# nagnet.net
KiCad netlist of a schematic drawn in Altium Designer
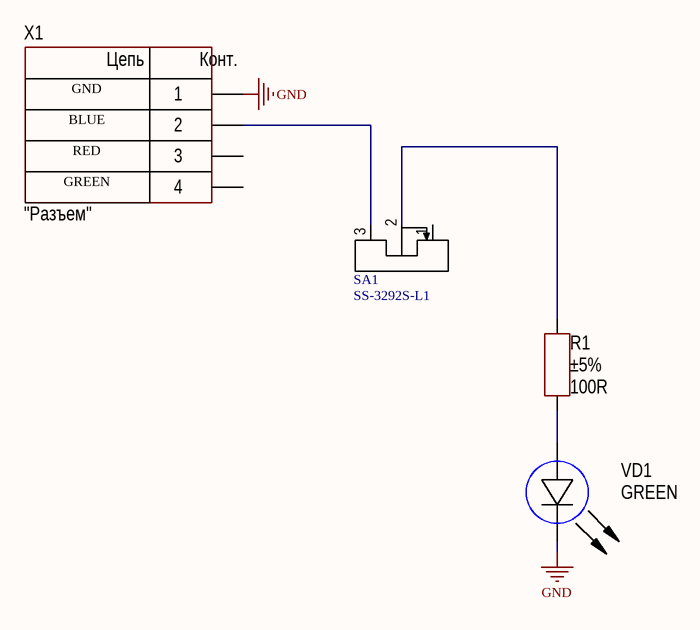
[diagram p0: nagnet.SchDoc]

(export (version "E")
  (design (tool "Eeschema 10.0.6"))
  (components
    (comp (ref "R1")
      (value "100R")
      (footprint "RES: 0603")
      (fields
        (field (name "MANUFACTURER") "Yageo")
        (field (name "PARTNUMBER") "RC0603JR-07100RL")
        (field (name "VALUEMANUFACTURERPARTNUMBER") "Resistor film, 100R, ±5%, 0603, 0.1W, -55...+125°C")
        (field (name "TOLERANCE") "±5%")
      )
      (libsource (lib "Resistor") (part "Resistor_0603"))
    )
    (comp (ref "SA1")
      (value "SS-3292S-L1")
      (footprint "SS-3292S-L1")
      (libsource (lib "switch") (part "SS-3292S-L1"))
    )
    (comp (ref "VD1")
      (value "~")
      (footprint "LED: 1206R")
      (fields
        (field (name "VALUEMANUFACTURERPARTNUMBER") "LED, *, *, *, -55...+150°C")
        (field (name "COLOR") "GREEN")
      )
      (libsource (lib "Diode") (part "LED_single"))
    )
    (comp (ref "X1")
      (value "~")
      (footprint "CON: PBS-4 R")
      (fields
        (field (name "MANUFACTURER") "Connfly")
        (field (name "VALUEMANUFACTURERPARTNUMBER") "Connector, 4pin, 2.54mm, 500VAC, 3A")
        (field (name "PARTNUMBER") "PBS-4")
        (field (name "COMMENTTEXT") "\"Разъем\"")
      )
      (libsource (lib "Connector") (part "PBS-4"))
    )
  )
  (nets
    (net (code "1") (name "GND") (class "Default")
      (node (ref "VD1") (pin "2") (pinfunction "C_2") (pintype "passive"))
      (node (ref "X1") (pin "1") (pinfunction "1_1") (pintype "passive"))
    )
    (net (code "2") (name "Net-(R1-Pad2)") (class "Default")
      (node (ref "R1") (pin "2") (pinfunction "2_2") (pintype "passive"))
      (node (ref "SA1") (pin "2") (pinfunction "2_2") (pintype "passive"))
    )
    (net (code "3") (name "Net-(SA1-Pad3)") (class "Default")
      (node (ref "SA1") (pin "3") (pinfunction "3_3") (pintype "passive"))
      (node (ref "X1") (pin "2") (pinfunction "2_2") (pintype "passive"))
    )
    (net (code "4") (name "Net-(VD1-A)") (class "Default")
      (node (ref "R1") (pin "1") (pinfunction "1_1") (pintype "passive"))
      (node (ref "VD1") (pin "1") (pinfunction "A_1") (pintype "passive"))
    )
    (net (code "5") (name "unconnected-(SA1-Pad1)") (class "Default")
      (node (ref "SA1") (pin "1") (pinfunction "1_1") (pintype "passive"))
    )
    (net (code "6") (name "unconnected-(X1-Pad3)") (class "Default")
      (node (ref "X1") (pin "3") (pinfunction "3_3") (pintype "power_in"))
    )
    (net (code "7") (name "unconnected-(X1-Pad4)") (class "Default")
      (node (ref "X1") (pin "4") (pinfunction "4_4") (pintype "power_in"))
    )
  )
)
